# Sheet1.net
KiCad netlist of a schematic drawn in Altium Designer
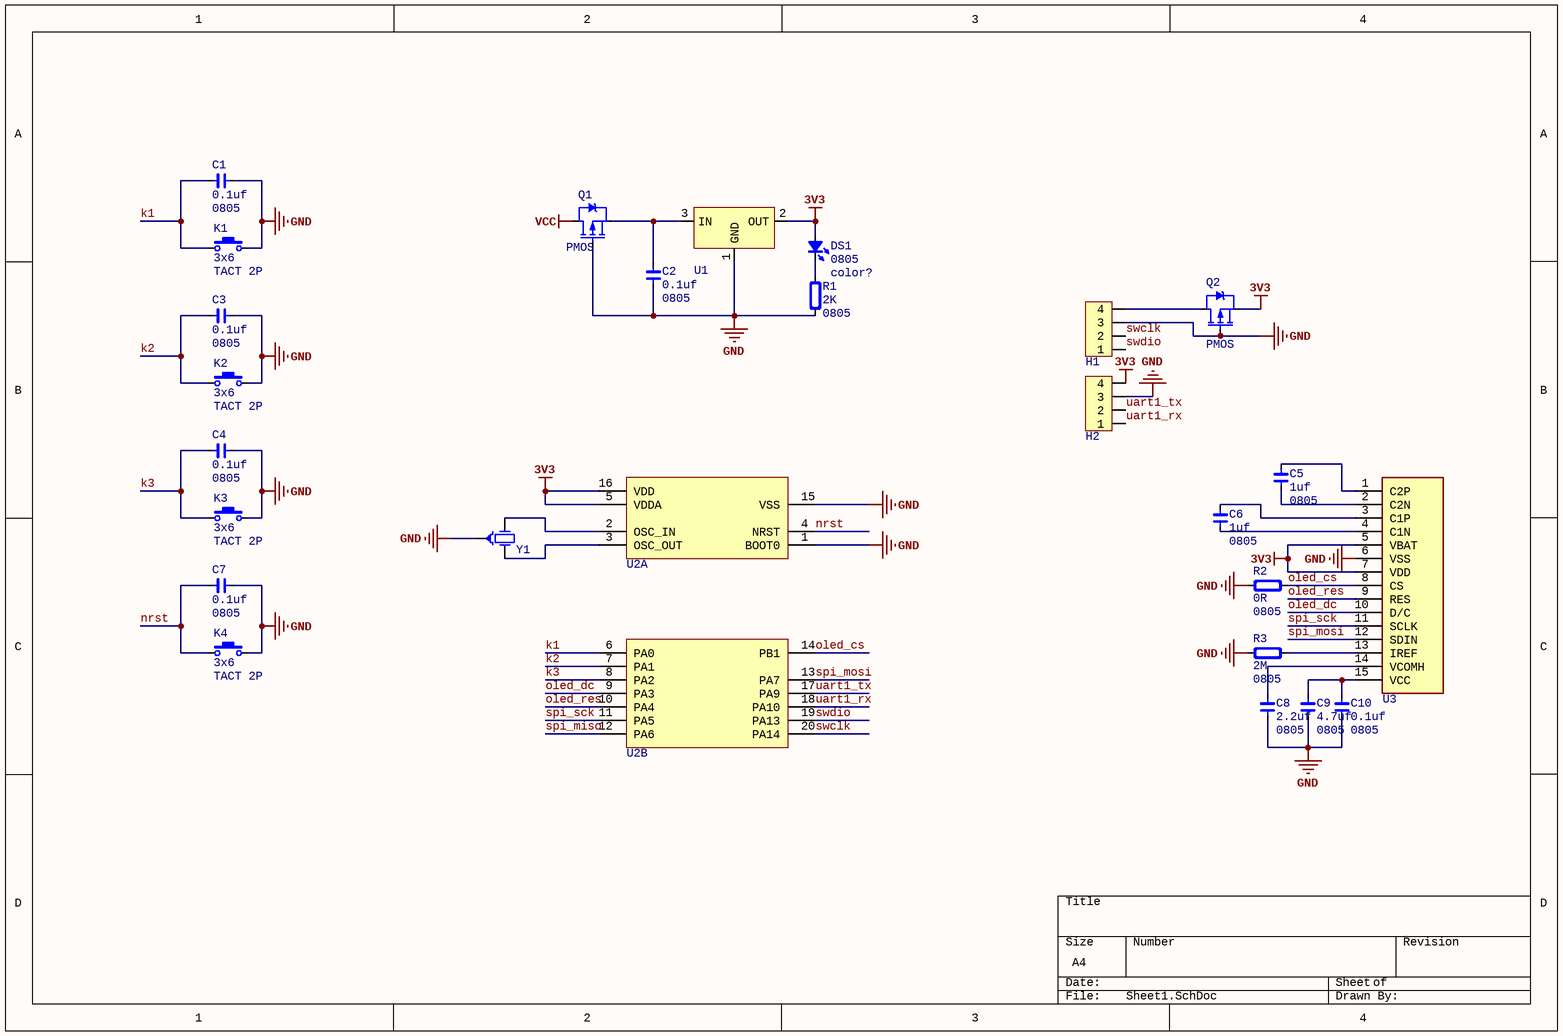
[diagram p0: Sheet1.SchDoc]

(export (version "E")
  (design (tool "Eeschema 10.0.6"))
  (components
    (comp (ref "C1")
      (value "0.1uf")
      (footprint "PCB_PassiveCap:CAP_0805")
      (description "Capacitor")
      (fields (field (name "TYPE") "0805") (field (name "Comment") "HDR2x10_2.54"))
      (libsource (lib "SCH_Passive") (part "Cap_0805"))
    )
    (comp (ref "C2")
      (value "0.1uf")
      (footprint "PCB_PassiveCap:CAP_0805")
      (description "Capacitor")
      (fields (field (name "TYPE") "0805") (field (name "Comment") "HDR2x10_2.54"))
      (libsource (lib "") (part "Cap_0805_2"))
    )
    (comp (ref "C3")
      (value "0.1uf")
      (footprint "PCB_PassiveCap:CAP_0805")
      (description "Capacitor")
      (fields (field (name "TYPE") "0805") (field (name "Comment") "HDR2x10_2.54"))
      (libsource (lib "SCH_Passive") (part "Cap_0805"))
    )
    (comp (ref "C4")
      (value "0.1uf")
      (footprint "PCB_PassiveCap:CAP_0805")
      (description "Capacitor")
      (fields (field (name "TYPE") "0805") (field (name "Comment") "HDR2x10_2.54"))
      (libsource (lib "SCH_Passive") (part "Cap_0805"))
    )
    (comp (ref "C5")
      (value "1uf")
      (footprint "PCB_PassiveCap:CAP_0805")
      (description "Capacitor")
      (fields (field (name "TYPE") "0805") (field (name "Comment") "HDR2x10_2.54"))
      (libsource (lib "") (part "Cap_0805_1"))
    )
    (comp (ref "C6")
      (value "1uf")
      (footprint "PCB_PassiveCap:CAP_0805")
      (description "Capacitor")
      (fields (field (name "TYPE") "0805") (field (name "Comment") "HDR2x10_2.54"))
      (libsource (lib "") (part "Cap_0805_1"))
    )
    (comp (ref "C7")
      (value "0.1uf")
      (footprint "PCB_PassiveCap:CAP_0805")
      (description "Capacitor")
      (fields (field (name "TYPE") "0805") (field (name "Comment") "HDR2x10_2.54"))
      (libsource (lib "SCH_Passive") (part "Cap_0805"))
    )
    (comp (ref "C8")
      (value "2.2uf")
      (footprint "PCB_PassiveCap:CAP_0805")
      (description "Capacitor")
      (fields (field (name "TYPE") "0805") (field (name "Comment") "HDR2x10_2.54"))
      (libsource (lib "") (part "Cap_0805_1"))
    )
    (comp (ref "C9")
      (value "4.7uf")
      (footprint "PCB_PassiveCap:CAP_0805")
      (description "Capacitor")
      (fields (field (name "TYPE") "0805") (field (name "Comment") "HDR2x10_2.54"))
      (libsource (lib "") (part "Cap_0805_1"))
    )
    (comp (ref "C10")
      (value "0.1uf")
      (footprint "PCB_PassiveCap:CAP_0805")
      (description "Capacitor")
      (fields (field (name "TYPE") "0805") (field (name "Comment") "HDR2x10_2.54"))
      (libsource (lib "") (part "Cap_0805_1"))
    )
    (comp (ref "DS1")
      (value "color?")
      (footprint "PCB_ActiveLED:LED_0805_RED")
      (description "LED")
      (fields (field (name "TYPE") "0805") (field (name "Comment") "HDR2x10_2.54"))
      (libsource (lib "SCH_Active") (part "LED_0805"))
    )
    (comp (ref "H1")
      (value "HDR2x10_2.54")
      (footprint "PCB_ConnectorHDR:HDR1x4_2.54_180")
      (description "Header")
      (libsource (lib "SCH_ConnectorHDR") (part "HDR1x4_2.54"))
    )
    (comp (ref "H2")
      (value "HDR2x10_2.54")
      (footprint "PCB_ConnectorHDR:HDR1x4_2.54_180")
      (description "Header")
      (libsource (lib "SCH_ConnectorHDR") (part "HDR1x4_2.54"))
    )
    (comp (ref "K1")
      (value "3x6")
      (footprint "PCB_Switch:ButtonTACT_3x6x2.5_180")
      (description "Button")
      (fields (field (name "TYPE") "TACT 2P") (field (name "Comment") "HDR2x10_2.54"))
      (libsource (lib "SCH_Switch") (part "ButtonTACT_3x6x2.5_180"))
    )
    (comp (ref "K2")
      (value "3x6")
      (footprint "PCB_Switch:ButtonTACT_3x6x2.5_180")
      (description "Button")
      (fields (field (name "TYPE") "TACT 2P") (field (name "Comment") "HDR2x10_2.54"))
      (libsource (lib "SCH_Switch") (part "ButtonTACT_3x6x2.5_180"))
    )
    (comp (ref "K3")
      (value "3x6")
      (footprint "PCB_Switch:ButtonTACT_3x6x2.5_180")
      (description "Button")
      (fields (field (name "TYPE") "TACT 2P") (field (name "Comment") "HDR2x10_2.54"))
      (libsource (lib "SCH_Switch") (part "ButtonTACT_3x6x2.5_180"))
    )
    (comp (ref "K4")
      (value "3x6")
      (footprint "PCB_Switch:ButtonTACT_3x6x2.5_180")
      (description "Button")
      (fields (field (name "TYPE") "TACT 2P") (field (name "Comment") "HDR2x10_2.54"))
      (libsource (lib "SCH_Switch") (part "ButtonTACT_3x6x2.5_180"))
    )
    (comp (ref "Q1")
      (value "PMOS")
      (footprint "PCB_IntegratedCircuit:SOT23-3")
      (description "MOSFET")
      (fields (field (name "Comment") "HDR2x10_2.54"))
      (libsource (lib "SCH_Active") (part "MOSFET_P_SOT23"))
    )
    (comp (ref "Q2")
      (value "PMOS")
      (footprint "PCB_IntegratedCircuit:SOT23-3")
      (description "MOSFET")
      (fields (field (name "Comment") "HDR2x10_2.54"))
      (libsource (lib "SCH_Active") (part "MOSFET_P_SOT23"))
    )
    (comp (ref "R1")
      (value "2K")
      (footprint "PCB_PassiveRes:RES_0805")
      (description "Resistor")
      (fields (field (name "TYPE") "0805") (field (name "Comment") "HDR2x10_2.54"))
      (libsource (lib "SCH_Passive") (part "Res_0805"))
    )
    (comp (ref "R2")
      (value "0R")
      (footprint "PCB_PassiveRes:RES_0805")
      (description "Resistor")
      (fields (field (name "TYPE") "0805") (field (name "Comment") "HDR2x10_2.54"))
      (libsource (lib "SCH_Passive") (part "Res_0805"))
    )
    (comp (ref "R3")
      (value "2M")
      (footprint "PCB_PassiveRes:RES_0805")
      (description "Resistor")
      (fields (field (name "TYPE") "0805") (field (name "Comment") "HDR2x10_2.54"))
      (libsource (lib "SCH_Passive") (part "Res_0805"))
    )
    (comp (ref "U1")
      (value "HDR2x10_2.54")
      (footprint "SOT23-3")
      (description "Power")
      (libsource (lib "SCH_IntegratedCircuit") (part "XC6206"))
    )
    (comp (ref "U2")
      (value "HDR2x10_2.54")
      (footprint "PCB_IntegratedCircuit:TSSOP_E170_P0.65_20")
      (description "MCU")
      (libsource (lib "SCH_IntegratedCircuit") (part "STM32F03xF"))
    )
    (comp (ref "U3")
      (value "HDR2x10_2.54")
      (footprint "OLED_0.91_128X64_SSD1306")
      (description "OLED")
      (libsource (lib "SCH_Module") (part "OLED_0.91_SSD1306"))
    )
    (comp (ref "Y1")
      (value "HDR2x10_2.54")
      (footprint "XTAL_3P_CSTCE_8M_3.2*1.3")
      (description "murata CSTCE 8M 3.2*1.3")
      (libsource (lib "SCH_Oscillator") (part "XTAL-3PIN"))
    )
  )
  (nets
    (net (code "1") (name "/k1") (class "Default")
      (node (ref "C1") (pin "1") (pinfunction "1_1") (pintype "passive"))
      (node (ref "K1") (pin "1") (pinfunction "1_1") (pintype "passive"))
      (node (ref "U2") (pin "6") (pinfunction "PA0_6") (pintype "passive"))
    )
    (net (code "2") (name "/k2") (class "Default")
      (node (ref "C3") (pin "1") (pinfunction "1_1") (pintype "passive"))
      (node (ref "K2") (pin "1") (pinfunction "1_1") (pintype "passive"))
      (node (ref "U2") (pin "7") (pinfunction "PA1_7") (pintype "passive"))
    )
    (net (code "3") (name "/k3") (class "Default")
      (node (ref "C4") (pin "1") (pinfunction "1_1") (pintype "passive"))
      (node (ref "K3") (pin "1") (pinfunction "1_1") (pintype "passive"))
      (node (ref "U2") (pin "8") (pinfunction "PA2_8") (pintype "passive"))
    )
    (net (code "4") (name "/nrst") (class "Default")
      (node (ref "C7") (pin "1") (pinfunction "1_1") (pintype "passive"))
      (node (ref "K4") (pin "1") (pinfunction "1_1") (pintype "passive"))
      (node (ref "U2") (pin "4") (pinfunction "NRST_4") (pintype "passive"))
    )
    (net (code "5") (name "/oled_cs") (class "Default")
      (node (ref "R2") (pin "1") (pinfunction "1_1") (pintype "passive"))
      (node (ref "U2") (pin "14") (pinfunction "PB1_14") (pintype "passive"))
      (node (ref "U3") (pin "8") (pinfunction "CS_8") (pintype "passive"))
    )
    (net (code "6") (name "/oled_dc") (class "Default")
      (node (ref "U2") (pin "9") (pinfunction "PA3_9") (pintype "passive"))
      (node (ref "U3") (pin "10") (pinfunction "D/C_10") (pintype "passive"))
    )
    (net (code "7") (name "/oled_res") (class "Default")
      (node (ref "U2") (pin "10") (pinfunction "PA4_10") (pintype "passive"))
      (node (ref "U3") (pin "9") (pinfunction "RES_9") (pintype "passive"))
    )
    (net (code "8") (name "/spi_miso") (class "Default")
      (node (ref "U2") (pin "12") (pinfunction "PA6_12") (pintype "passive"))
    )
    (net (code "9") (name "/spi_mosi") (class "Default")
      (node (ref "U2") (pin "13") (pinfunction "PA7_13") (pintype "passive"))
      (node (ref "U3") (pin "12") (pinfunction "SDIN_12") (pintype "passive"))
    )
    (net (code "10") (name "/spi_sck") (class "Default")
      (node (ref "U2") (pin "11") (pinfunction "PA5_11") (pintype "passive"))
      (node (ref "U3") (pin "11") (pinfunction "SCLK_11") (pintype "passive"))
    )
    (net (code "11") (name "/swclk") (class "Default")
      (node (ref "H1") (pin "2") (pinfunction "2_2") (pintype "passive"))
      (node (ref "U2") (pin "20") (pinfunction "PA14_20") (pintype "passive"))
    )
    (net (code "12") (name "/swdio") (class "Default")
      (node (ref "H1") (pin "1") (pinfunction "1_1") (pintype "passive"))
      (node (ref "U2") (pin "19") (pinfunction "PA13_19") (pintype "passive"))
    )
    (net (code "13") (name "/uart1_rx") (class "Default")
      (node (ref "H2") (pin "1") (pinfunction "1_1") (pintype "passive"))
      (node (ref "U2") (pin "18") (pinfunction "PA10_18") (pintype "passive"))
    )
    (net (code "14") (name "/uart1_tx") (class "Default")
      (node (ref "H2") (pin "2") (pinfunction "2_2") (pintype "passive"))
      (node (ref "U2") (pin "17") (pinfunction "PA9_17") (pintype "passive"))
    )
    (net (code "15") (name "3V3") (class "Default")
      (node (ref "DS1") (pin "1") (pinfunction "A_1") (pintype "passive"))
      (node (ref "H2") (pin "4") (pinfunction "4_4") (pintype "passive"))
      (node (ref "Q2") (pin "2") (pinfunction "S_2") (pintype "passive"))
      (node (ref "U1") (pin "2") (pinfunction "OUT_2") (pintype "power_in"))
      (node (ref "U2") (pin "16") (pinfunction "VDD_16") (pintype "passive"))
      (node (ref "U2") (pin "5") (pinfunction "VDDA_5") (pintype "passive"))
      (node (ref "U3") (pin "5") (pinfunction "VBAT_5") (pintype "passive"))
      (node (ref "U3") (pin "7") (pinfunction "VDD_7") (pintype "passive"))
    )
    (net (code "16") (name "GND") (class "Default")
      (node (ref "C1") (pin "2") (pinfunction "2_2") (pintype "passive"))
      (node (ref "C10") (pin "2") (pinfunction "2_2") (pintype "passive"))
      (node (ref "C2") (pin "1") (pinfunction "1_1") (pintype "passive"))
      (node (ref "C3") (pin "2") (pinfunction "2_2") (pintype "passive"))
      (node (ref "C4") (pin "2") (pinfunction "2_2") (pintype "passive"))
      (node (ref "C7") (pin "2") (pinfunction "2_2") (pintype "passive"))
      (node (ref "C8") (pin "2") (pinfunction "2_2") (pintype "passive"))
      (node (ref "C9") (pin "2") (pinfunction "2_2") (pintype "passive"))
      (node (ref "H1") (pin "3") (pinfunction "3_3") (pintype "passive"))
      (node (ref "H2") (pin "3") (pinfunction "3_3") (pintype "passive"))
      (node (ref "K1") (pin "2") (pinfunction "2_2") (pintype "passive"))
      (node (ref "K2") (pin "2") (pinfunction "2_2") (pintype "passive"))
      (node (ref "K3") (pin "2") (pinfunction "2_2") (pintype "passive"))
      (node (ref "K4") (pin "2") (pinfunction "2_2") (pintype "passive"))
      (node (ref "Q1") (pin "1") (pinfunction "G_1") (pintype "passive"))
      (node (ref "Q2") (pin "1") (pinfunction "G_1") (pintype "passive"))
      (node (ref "R1") (pin "1") (pinfunction "1_1") (pintype "passive"))
      (node (ref "R2") (pin "2") (pinfunction "2_2") (pintype "passive"))
      (node (ref "R3") (pin "2") (pinfunction "2_2") (pintype "passive"))
      (node (ref "U1") (pin "1") (pinfunction "GND_1") (pintype "power_in"))
      (node (ref "U2") (pin "1") (pinfunction "BOOT0_1") (pintype "passive"))
      (node (ref "U2") (pin "15") (pinfunction "VSS_15") (pintype "passive"))
      (node (ref "U3") (pin "6") (pinfunction "VSS_6") (pintype "passive"))
      (node (ref "Y1") (pin "2") (pinfunction "GND_2") (pintype "passive"))
    )
    (net (code "17") (name "Net-(DS1-K)") (class "Default")
      (node (ref "DS1") (pin "2") (pinfunction "K_2") (pintype "passive"))
      (node (ref "R1") (pin "2") (pinfunction "2_2") (pintype "passive"))
    )
    (net (code "18") (name "Net-(Q1-S)") (class "Default")
      (node (ref "C2") (pin "2") (pinfunction "2_2") (pintype "passive"))
      (node (ref "Q1") (pin "2") (pinfunction "S_2") (pintype "passive"))
      (node (ref "U1") (pin "3") (pinfunction "IN_3") (pintype "power_in"))
    )
    (net (code "19") (name "Net-(Q2-D)") (class "Default")
      (node (ref "H1") (pin "4") (pinfunction "4_4") (pintype "passive"))
      (node (ref "Q2") (pin "3") (pinfunction "D_3") (pintype "passive"))
    )
    (net (code "20") (name "Net-(U2A-OSC_IN)") (class "Default")
      (node (ref "U2") (pin "2") (pinfunction "OSC_IN_2") (pintype "passive"))
      (node (ref "Y1") (pin "1") (pinfunction "OSC1_1") (pintype "passive"))
    )
    (net (code "21") (name "Net-(U2A-OSC_OUT)") (class "Default")
      (node (ref "U2") (pin "3") (pinfunction "OSC_OUT_3") (pintype "passive"))
      (node (ref "Y1") (pin "3") (pinfunction "OSC2_3") (pintype "passive"))
    )
    (net (code "22") (name "Net-(U3-C1N)") (class "Default")
      (node (ref "C6") (pin "2") (pinfunction "2_2") (pintype "passive"))
      (node (ref "U3") (pin "4") (pinfunction "C1N_4") (pintype "passive"))
    )
    (net (code "23") (name "Net-(U3-C1P)") (class "Default")
      (node (ref "C6") (pin "1") (pinfunction "1_1") (pintype "passive"))
      (node (ref "U3") (pin "3") (pinfunction "C1P_3") (pintype "passive"))
    )
    (net (code "24") (name "Net-(U3-C2N)") (class "Default")
      (node (ref "C5") (pin "2") (pinfunction "2_2") (pintype "passive"))
      (node (ref "U3") (pin "2") (pinfunction "C2N_2") (pintype "passive"))
    )
    (net (code "25") (name "Net-(U3-C2P)") (class "Default")
      (node (ref "C5") (pin "1") (pinfunction "1_1") (pintype "passive"))
      (node (ref "U3") (pin "1") (pinfunction "C2P_1") (pintype "passive"))
    )
    (net (code "26") (name "Net-(U3-IREF)") (class "Default")
      (node (ref "R3") (pin "1") (pinfunction "1_1") (pintype "passive"))
      (node (ref "U3") (pin "13") (pinfunction "IREF_13") (pintype "passive"))
    )
    (net (code "27") (name "Net-(U3-VCC)") (class "Default")
      (node (ref "C10") (pin "1") (pinfunction "1_1") (pintype "passive"))
      (node (ref "C9") (pin "1") (pinfunction "1_1") (pintype "passive"))
      (node (ref "U3") (pin "15") (pinfunction "VCC_15") (pintype "passive"))
    )
    (net (code "28") (name "Net-(U3-VCOMH)") (class "Default")
      (node (ref "C8") (pin "1") (pinfunction "1_1") (pintype "passive"))
      (node (ref "U3") (pin "14") (pinfunction "VCOMH_14") (pintype "passive"))
    )
    (net (code "29") (name "VCC") (class "Default")
      (node (ref "Q1") (pin "3") (pinfunction "D_3") (pintype "passive"))
    )
  )
)
